# PWM_Inputs.net
KiCad netlist of a schematic drawn in Altium Designer
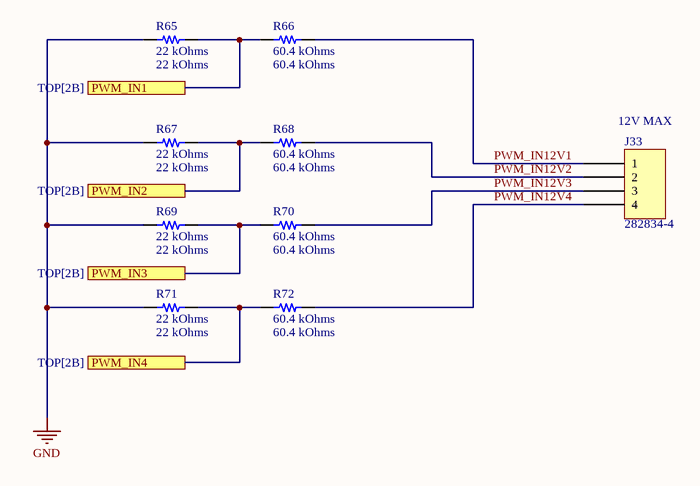
[diagram p0: PWM Inputs.SchDoc]

(export (version "E")
  (design (tool "Eeschema 10.0.6"))
  (components
    (comp (ref "J33")
      (value "282834-4")
      (footprint "TE 282834-4")
      (description "TERM BLK 4P SIDE ENT 2.54MM PCB")
      (fields (field (name "MANUFACTURER") "TE Connectivity AMP Connectors") (field (name "VOLTAGE") "150V"))
      (libsource (lib "altium_library") (part "4 Pin"))
    )
    (comp (ref "R65")
      (value "22 kOhms")
      (footprint "RES 0603_1608")
      (description "RES 22K OHM 1% 1/5W 0603")
      (fields (field (name "PART NUMBER") "AC0603FR-7W22KL") (field (name "ALTIUM_VALUE") "22 kOhms"))
      (libsource (lib "altium_library") (part "Resistor"))
    )
    (comp (ref "R66")
      (value "60.4 kOhms")
      (footprint "RES 0603_1608")
      (description "RES SMD 60.4K OHM 1% 1/10W 0603")
      (fields (field (name "PART NUMBER") "AC0603FR-0760K4L") (field (name "ALTIUM_VALUE") "60.4 kOhms"))
      (libsource (lib "altium_library") (part "Resistor"))
    )
    (comp (ref "R67")
      (value "22 kOhms")
      (footprint "RES 0603_1608")
      (description "RES 22K OHM 1% 1/5W 0603")
      (fields (field (name "PART NUMBER") "AC0603FR-7W22KL") (field (name "ALTIUM_VALUE") "22 kOhms"))
      (libsource (lib "altium_library") (part "Resistor"))
    )
    (comp (ref "R68")
      (value "60.4 kOhms")
      (footprint "RES 0603_1608")
      (description "RES SMD 60.4K OHM 1% 1/10W 0603")
      (fields (field (name "PART NUMBER") "AC0603FR-0760K4L") (field (name "ALTIUM_VALUE") "60.4 kOhms"))
      (libsource (lib "altium_library") (part "Resistor"))
    )
    (comp (ref "R69")
      (value "22 kOhms")
      (footprint "RES 0603_1608")
      (description "RES 22K OHM 1% 1/5W 0603")
      (fields (field (name "PART NUMBER") "AC0603FR-7W22KL") (field (name "ALTIUM_VALUE") "22 kOhms"))
      (libsource (lib "altium_library") (part "Resistor"))
    )
    (comp (ref "R70")
      (value "60.4 kOhms")
      (footprint "RES 0603_1608")
      (description "RES SMD 60.4K OHM 1% 1/10W 0603")
      (fields (field (name "PART NUMBER") "AC0603FR-0760K4L") (field (name "ALTIUM_VALUE") "60.4 kOhms"))
      (libsource (lib "altium_library") (part "Resistor"))
    )
    (comp (ref "R71")
      (value "22 kOhms")
      (footprint "RES 0603_1608")
      (description "RES 22K OHM 1% 1/5W 0603")
      (fields (field (name "PART NUMBER") "AC0603FR-7W22KL") (field (name "ALTIUM_VALUE") "22 kOhms"))
      (libsource (lib "altium_library") (part "Resistor"))
    )
    (comp (ref "R72")
      (value "60.4 kOhms")
      (footprint "RES 0603_1608")
      (description "RES SMD 60.4K OHM 1% 1/10W 0603")
      (fields (field (name "PART NUMBER") "AC0603FR-0760K4L") (field (name "ALTIUM_VALUE") "60.4 kOhms"))
      (libsource (lib "altium_library") (part "Resistor"))
    )
  )
  (nets
    (net (code "1") (name "/PWM_IN1") (class "Default")
      (node (ref "R65") (pin "1") (pinfunction "1_1") (pintype "passive"))
      (node (ref "R66") (pin "2") (pinfunction "2_2") (pintype "passive"))
    )
    (net (code "2") (name "/PWM_IN2") (class "Default")
      (node (ref "R67") (pin "1") (pinfunction "1_1") (pintype "passive"))
      (node (ref "R68") (pin "2") (pinfunction "2_2") (pintype "passive"))
    )
    (net (code "3") (name "/PWM_IN3") (class "Default")
      (node (ref "R69") (pin "1") (pinfunction "1_1") (pintype "passive"))
      (node (ref "R70") (pin "2") (pinfunction "2_2") (pintype "passive"))
    )
    (net (code "4") (name "/PWM_IN4") (class "Default")
      (node (ref "R71") (pin "1") (pinfunction "1_1") (pintype "passive"))
      (node (ref "R72") (pin "2") (pinfunction "2_2") (pintype "passive"))
    )
    (net (code "5") (name "/PWM_IN12V1") (class "Default")
      (node (ref "J33") (pin "1") (pinfunction "1_1") (pintype "passive"))
      (node (ref "R66") (pin "1") (pinfunction "1_1") (pintype "passive"))
    )
    (net (code "6") (name "/PWM_IN12V2") (class "Default")
      (node (ref "J33") (pin "2") (pinfunction "2_2") (pintype "passive"))
      (node (ref "R68") (pin "1") (pinfunction "1_1") (pintype "passive"))
    )
    (net (code "7") (name "/PWM_IN12V3") (class "Default")
      (node (ref "J33") (pin "3") (pinfunction "3_3") (pintype "passive"))
      (node (ref "R70") (pin "1") (pinfunction "1_1") (pintype "passive"))
    )
    (net (code "8") (name "/PWM_IN12V4") (class "Default")
      (node (ref "J33") (pin "4") (pinfunction "4_4") (pintype "passive"))
      (node (ref "R72") (pin "1") (pinfunction "1_1") (pintype "passive"))
    )
    (net (code "9") (name "GND") (class "Default")
      (node (ref "R65") (pin "2") (pinfunction "2_2") (pintype "passive"))
      (node (ref "R67") (pin "2") (pinfunction "2_2") (pintype "passive"))
      (node (ref "R69") (pin "2") (pinfunction "2_2") (pintype "passive"))
      (node (ref "R71") (pin "2") (pinfunction "2_2") (pintype "passive"))
    )
  )
)
